# v1_TH.net
KiCad netlist of a schematic drawn in EAGLE
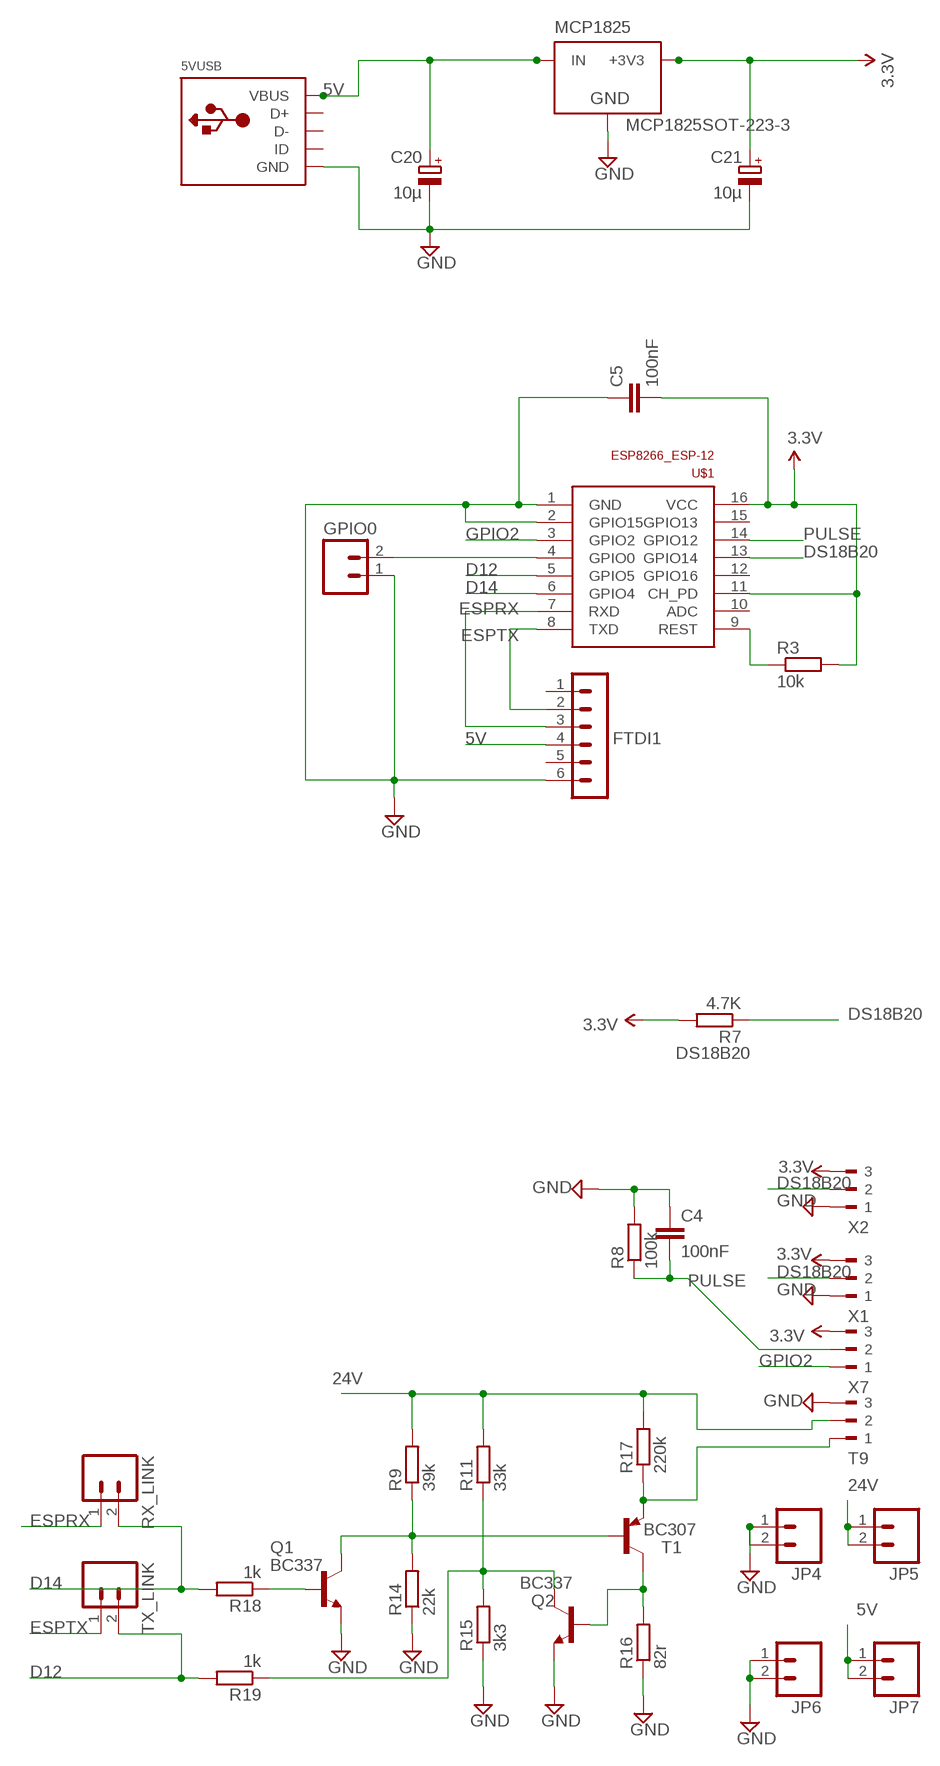
[diagram p0: schematic, sheet 1]

(export (version "E")
  (design (tool "Eeschema 10.0.6"))
  (components
    (comp (ref "5VUSB")
      (value "USBMOLEX")
      (footprint "eagle-import:USB-MINIB-THM-MOLEX")
      (libsource (lib "eagle-import") (part "USBMOLEX"))
    )
    (comp (ref "C4")
      (value "100nF")
      (footprint "eagle-import:C025-024X044")
      (libsource (lib "eagle-import") (part "C-EU025-024X044"))
    )
    (comp (ref "C5")
      (value "100nF")
      (footprint "eagle-import:C025-024X044")
      (libsource (lib "eagle-import") (part "C-EU025-024X044"))
    )
    (comp (ref "C20")
      (value "10µ")
      (footprint "eagle-import:E1,8-4")
      (libsource (lib "eagle-import") (part "CPOL-EUE1.8-4"))
    )
    (comp (ref "C21")
      (value "10µ")
      (footprint "eagle-import:E1,8-4")
      (libsource (lib "eagle-import") (part "CPOL-EUE1.8-4"))
    )
    (comp (ref "FTDI1")
      (value "FTDI")
      (footprint "eagle-import:MA06-1")
      (libsource (lib "eagle-import") (part "MA06-1"))
    )
    (comp (ref "GPIO0")
      (value "M02PTH")
      (footprint "eagle-import:1X02")
      (libsource (lib "eagle-import") (part "M02PTH"))
    )
    (comp (ref "JP4")
      (value "M02PTH")
      (footprint "eagle-import:1X02")
      (libsource (lib "eagle-import") (part "M02PTH"))
    )
    (comp (ref "JP5")
      (value "M02PTH")
      (footprint "eagle-import:1X02")
      (libsource (lib "eagle-import") (part "M02PTH"))
    )
    (comp (ref "JP6")
      (value "M02PTH")
      (footprint "eagle-import:1X02")
      (libsource (lib "eagle-import") (part "M02PTH"))
    )
    (comp (ref "JP7")
      (value "M02PTH")
      (footprint "eagle-import:1X02")
      (libsource (lib "eagle-import") (part "M02PTH"))
    )
    (comp (ref "MCP1825")
      (value "MCP1825SOT-223-3")
      (footprint "eagle-import:SOT-223")
      (libsource (lib "eagle-import") (part "MCP1825SOT-223-3"))
    )
    (comp (ref "Q1")
      (value "BC337")
      (footprint "eagle-import:TO92")
      (libsource (lib "eagle-import") (part "BC337"))
    )
    (comp (ref "Q2")
      (value "BC337")
      (footprint "eagle-import:TO92")
      (libsource (lib "eagle-import") (part "BC337"))
    )
    (comp (ref "R3")
      (value "10k")
      (footprint "eagle-import:0204_7")
      (libsource (lib "eagle-import") (part "R-EU_0204/7"))
    )
    (comp (ref "R7")
      (value "4.7K")
      (footprint "eagle-import:0204_7")
      (libsource (lib "eagle-import") (part "resistor_R-EU_0204/7"))
    )
    (comp (ref "R8")
      (value "100k")
      (footprint "eagle-import:0207_2V")
      (libsource (lib "eagle-import") (part "R-EU_0207/2V"))
    )
    (comp (ref "R9")
      (value "39k")
      (footprint "eagle-import:0204_7")
      (libsource (lib "eagle-import") (part "resistor_R-EU_0204/7"))
    )
    (comp (ref "R11")
      (value "33k")
      (footprint "eagle-import:0204_7")
      (libsource (lib "eagle-import") (part "resistor_R-EU_0204/7"))
    )
    (comp (ref "R14")
      (value "22k")
      (footprint "eagle-import:0204_7")
      (libsource (lib "eagle-import") (part "resistor_R-EU_0204/7"))
    )
    (comp (ref "R15")
      (value "3k3")
      (footprint "eagle-import:0204_7")
      (libsource (lib "eagle-import") (part "resistor_R-EU_0204/7"))
    )
    (comp (ref "R16")
      (value "82r")
      (footprint "eagle-import:0204_7")
      (libsource (lib "eagle-import") (part "resistor_R-EU_0204/7"))
    )
    (comp (ref "R17")
      (value "220k")
      (footprint "eagle-import:0204_7")
      (libsource (lib "eagle-import") (part "resistor_R-EU_0204/7"))
    )
    (comp (ref "R18")
      (value "1k")
      (footprint "eagle-import:0204_7")
      (libsource (lib "eagle-import") (part "resistor_R-EU_0204/7"))
    )
    (comp (ref "R19")
      (value "1k")
      (footprint "eagle-import:0204_7")
      (libsource (lib "eagle-import") (part "resistor_R-EU_0204/7"))
    )
    (comp (ref "RX_LINK")
      (value "M02PTH")
      (footprint "eagle-import:1X02")
      (libsource (lib "eagle-import") (part "M02PTH"))
    )
    (comp (ref "T1")
      (value "BC307")
      (footprint "eagle-import:TO92")
      (libsource (lib "eagle-import") (part "BC307"))
    )
    (comp (ref "T9")
      (value "180-3")
      (footprint "eagle-import:180-3")
      (libsource (lib "eagle-import") (part "180-3"))
    )
    (comp (ref "TX_LINK")
      (value "M02PTH")
      (footprint "eagle-import:1X02")
      (libsource (lib "eagle-import") (part "M02PTH"))
    )
    (comp (ref "U$1")
      (value "ESP8266_ESP-12")
      (footprint "eagle-import:ESP8266-ESP12")
      (libsource (lib "eagle-import") (part "ESP8266_ESP-12"))
    )
    (comp (ref "X1")
      (value "180-3")
      (footprint "eagle-import:180-3")
      (libsource (lib "eagle-import") (part "180-3"))
    )
    (comp (ref "X2")
      (value "180-3")
      (footprint "eagle-import:180-3")
      (libsource (lib "eagle-import") (part "180-3"))
    )
    (comp (ref "X7")
      (value "180-3")
      (footprint "eagle-import:180-3")
      (libsource (lib "eagle-import") (part "180-3"))
    )
  )
  (nets
    (net (code "1") (name "/5V") (class "Default")
      (node (ref "5VUSB") (pin "VBUS") (pinfunction "VBUS_VBUS") (pintype "power_in"))
      (node (ref "C20") (pin "+") (pinfunction "+_+") (pintype "passive"))
      (node (ref "FTDI1") (pin "4") (pinfunction "4_4") (pintype "passive"))
      (node (ref "JP7") (pin "1") (pinfunction "1_1") (pintype "passive"))
      (node (ref "JP7") (pin "2") (pinfunction "2_2") (pintype "passive"))
      (node (ref "MCP1825") (pin "1") (pinfunction "IN_1") (pintype "power_in"))
    )
    (net (code "2") (name "/24V") (class "Default")
      (node (ref "JP5") (pin "1") (pinfunction "1_1") (pintype "passive"))
      (node (ref "JP5") (pin "2") (pinfunction "2_2") (pintype "passive"))
      (node (ref "R11") (pin "2") (pinfunction "2_2") (pintype "passive"))
      (node (ref "R17") (pin "2") (pinfunction "2_2") (pintype "passive"))
      (node (ref "R9") (pin "2") (pinfunction "2_2") (pintype "passive"))
      (node (ref "T9") (pin "2") (pinfunction "2_2") (pintype "passive"))
    )
    (net (code "3") (name "/D12") (class "Default")
      (node (ref "R19") (pin "2") (pinfunction "2_2") (pintype "passive"))
      (node (ref "TX_LINK") (pin "2") (pinfunction "2_2") (pintype "passive"))
      (node (ref "U$1") (pin "5") (pinfunction "GPIO5_5") (pintype "bidirectional"))
    )
    (net (code "4") (name "/D14") (class "Default")
      (node (ref "R18") (pin "2") (pinfunction "2_2") (pintype "passive"))
      (node (ref "RX_LINK") (pin "2") (pinfunction "2_2") (pintype "passive"))
      (node (ref "U$1") (pin "6") (pinfunction "GPIO4_6") (pintype "bidirectional"))
    )
    (net (code "5") (name "/DS18B20") (class "Default")
      (node (ref "R7") (pin "1") (pinfunction "1_1") (pintype "passive"))
      (node (ref "U$1") (pin "13") (pinfunction "GPIO14_13") (pintype "bidirectional"))
      (node (ref "X1") (pin "2") (pinfunction "2_2") (pintype "passive"))
      (node (ref "X2") (pin "2") (pinfunction "2_2") (pintype "passive"))
    )
    (net (code "6") (name "/ESPRX") (class "Default")
      (node (ref "FTDI1") (pin "3") (pinfunction "3_3") (pintype "passive"))
      (node (ref "RX_LINK") (pin "1") (pinfunction "1_1") (pintype "passive"))
      (node (ref "U$1") (pin "7") (pinfunction "RXD_7") (pintype "bidirectional"))
    )
    (net (code "7") (name "/ESPTX") (class "Default")
      (node (ref "FTDI1") (pin "2") (pinfunction "2_2") (pintype "passive"))
      (node (ref "TX_LINK") (pin "1") (pinfunction "1_1") (pintype "passive"))
      (node (ref "U$1") (pin "8") (pinfunction "TXD_8") (pintype "bidirectional"))
    )
    (net (code "8") (name "/GPIO2") (class "Default")
      (node (ref "U$1") (pin "3") (pinfunction "GPIO2_3") (pintype "bidirectional"))
      (node (ref "X7") (pin "1") (pinfunction "1_1") (pintype "passive"))
    )
    (net (code "9") (name "/PULSE") (class "Default")
      (node (ref "C4") (pin "2") (pinfunction "2_2") (pintype "passive"))
      (node (ref "R8") (pin "1") (pinfunction "1_1") (pintype "passive"))
      (node (ref "U$1") (pin "14") (pinfunction "GPIO12_14") (pintype "bidirectional"))
      (node (ref "X7") (pin "2") (pinfunction "2_2") (pintype "passive"))
    )
    (net (code "10") (name "3.3V") (class "Default")
      (node (ref "C21") (pin "+") (pinfunction "+_+") (pintype "passive"))
      (node (ref "C5") (pin "2") (pinfunction "2_2") (pintype "passive"))
      (node (ref "MCP1825") (pin "3") (pinfunction "+3V3_3") (pintype "power_in"))
      (node (ref "R3") (pin "2") (pinfunction "2_2") (pintype "passive"))
      (node (ref "R7") (pin "2") (pinfunction "2_2") (pintype "passive"))
      (node (ref "U$1") (pin "11") (pinfunction "CH_PD_11") (pintype "bidirectional"))
      (node (ref "U$1") (pin "16") (pinfunction "VCC_16") (pintype "bidirectional"))
      (node (ref "X1") (pin "3") (pinfunction "3_3") (pintype "passive"))
      (node (ref "X2") (pin "3") (pinfunction "3_3") (pintype "passive"))
      (node (ref "X7") (pin "3") (pinfunction "3_3") (pintype "passive"))
    )
    (net (code "11") (name "GND") (class "Default")
      (node (ref "5VUSB") (pin "GND") (pinfunction "GND_GND") (pintype "power_in"))
      (node (ref "C20") (pin "-") (pinfunction "-_-") (pintype "passive"))
      (node (ref "C21") (pin "-") (pinfunction "-_-") (pintype "passive"))
      (node (ref "C4") (pin "1") (pinfunction "1_1") (pintype "passive"))
      (node (ref "C5") (pin "1") (pinfunction "1_1") (pintype "passive"))
      (node (ref "FTDI1") (pin "6") (pinfunction "6_6") (pintype "passive"))
      (node (ref "GPIO0") (pin "1") (pinfunction "1_1") (pintype "passive"))
      (node (ref "JP4") (pin "1") (pinfunction "1_1") (pintype "passive"))
      (node (ref "JP4") (pin "2") (pinfunction "2_2") (pintype "passive"))
      (node (ref "JP6") (pin "1") (pinfunction "1_1") (pintype "passive"))
      (node (ref "JP6") (pin "2") (pinfunction "2_2") (pintype "passive"))
      (node (ref "MCP1825") (pin "2") (pinfunction "GND_2") (pintype "power_in"))
      (node (ref "Q1") (pin "1") (pinfunction "E_1") (pintype "passive"))
      (node (ref "Q2") (pin "1") (pinfunction "E_1") (pintype "passive"))
      (node (ref "R14") (pin "1") (pinfunction "1_1") (pintype "passive"))
      (node (ref "R15") (pin "1") (pinfunction "1_1") (pintype "passive"))
      (node (ref "R16") (pin "1") (pinfunction "1_1") (pintype "passive"))
      (node (ref "R8") (pin "2") (pinfunction "2_2") (pintype "passive"))
      (node (ref "T9") (pin "3") (pinfunction "3_3") (pintype "passive"))
      (node (ref "U$1") (pin "1") (pinfunction "GND_1") (pintype "bidirectional"))
      (node (ref "U$1") (pin "2") (pinfunction "GPIO15_2") (pintype "bidirectional"))
      (node (ref "X1") (pin "1") (pinfunction "1_1") (pintype "passive"))
      (node (ref "X2") (pin "1") (pinfunction "1_1") (pintype "passive"))
    )
    (net (code "12") (name "Net-(Q1-B)") (class "Default")
      (node (ref "Q1") (pin "2") (pinfunction "B_2") (pintype "passive"))
      (node (ref "R18") (pin "1") (pinfunction "1_1") (pintype "passive"))
    )
    (net (code "13") (name "Net-(Q1-C)") (class "Default")
      (node (ref "Q1") (pin "3") (pinfunction "C_3") (pintype "passive"))
      (node (ref "R14") (pin "2") (pinfunction "2_2") (pintype "passive"))
      (node (ref "R9") (pin "1") (pinfunction "1_1") (pintype "passive"))
      (node (ref "T1") (pin "2") (pinfunction "B_2") (pintype "passive"))
    )
    (net (code "14") (name "Net-(Q2-B)") (class "Default")
      (node (ref "Q2") (pin "2") (pinfunction "B_2") (pintype "passive"))
      (node (ref "R16") (pin "2") (pinfunction "2_2") (pintype "passive"))
      (node (ref "T1") (pin "3") (pinfunction "C_3") (pintype "passive"))
    )
    (net (code "15") (name "Net-(Q2-C)") (class "Default")
      (node (ref "Q2") (pin "3") (pinfunction "C_3") (pintype "passive"))
      (node (ref "R11") (pin "1") (pinfunction "1_1") (pintype "passive"))
      (node (ref "R15") (pin "2") (pinfunction "2_2") (pintype "passive"))
      (node (ref "R19") (pin "1") (pinfunction "1_1") (pintype "passive"))
    )
    (net (code "16") (name "Net-(T1-E)") (class "Default")
      (node (ref "R17") (pin "1") (pinfunction "1_1") (pintype "passive"))
      (node (ref "T1") (pin "1") (pinfunction "E_1") (pintype "passive"))
      (node (ref "T9") (pin "1") (pinfunction "1_1") (pintype "passive"))
    )
    (net (code "17") (name "Net-(U$1-GPIO0)") (class "Default")
      (node (ref "GPIO0") (pin "2") (pinfunction "2_2") (pintype "passive"))
      (node (ref "U$1") (pin "4") (pinfunction "GPIO0_4") (pintype "bidirectional"))
    )
    (net (code "18") (name "Net-(U$1-REST)") (class "Default")
      (node (ref "R3") (pin "1") (pinfunction "1_1") (pintype "passive"))
      (node (ref "U$1") (pin "9") (pinfunction "REST_9") (pintype "bidirectional"))
    )
    (net (code "19") (name "unconnected-(5VUSB-PadD+)") (class "Default")
      (node (ref "5VUSB") (pin "D+") (pinfunction "D+_D+") (pintype "bidirectional"))
    )
    (net (code "20") (name "unconnected-(5VUSB-PadD-)") (class "Default")
      (node (ref "5VUSB") (pin "D-") (pinfunction "D-_D-") (pintype "bidirectional"))
    )
    (net (code "21") (name "unconnected-(5VUSB-PadID)") (class "Default")
      (node (ref "5VUSB") (pin "ID") (pinfunction "ID_ID") (pintype "bidirectional"))
    )
    (net (code "22") (name "unconnected-(FTDI1-Pad1)") (class "Default")
      (node (ref "FTDI1") (pin "1") (pinfunction "1_1") (pintype "passive"))
    )
    (net (code "23") (name "unconnected-(FTDI1-Pad5)") (class "Default")
      (node (ref "FTDI1") (pin "5") (pinfunction "5_5") (pintype "passive"))
    )
    (net (code "24") (name "unconnected-(U$1-ADC-Pad10)") (class "Default")
      (node (ref "U$1") (pin "10") (pinfunction "ADC_10") (pintype "bidirectional"))
    )
    (net (code "25") (name "unconnected-(U$1-GPIO13-Pad15)") (class "Default")
      (node (ref "U$1") (pin "15") (pinfunction "GPIO13_15") (pintype "bidirectional"))
    )
    (net (code "26") (name "unconnected-(U$1-GPIO16-Pad12)") (class "Default")
      (node (ref "U$1") (pin "12") (pinfunction "GPIO16_12") (pintype "bidirectional"))
    )
  )
)
